# CATS-GS-Overview.net
KiCad netlist of a schematic drawn in Altium Designer
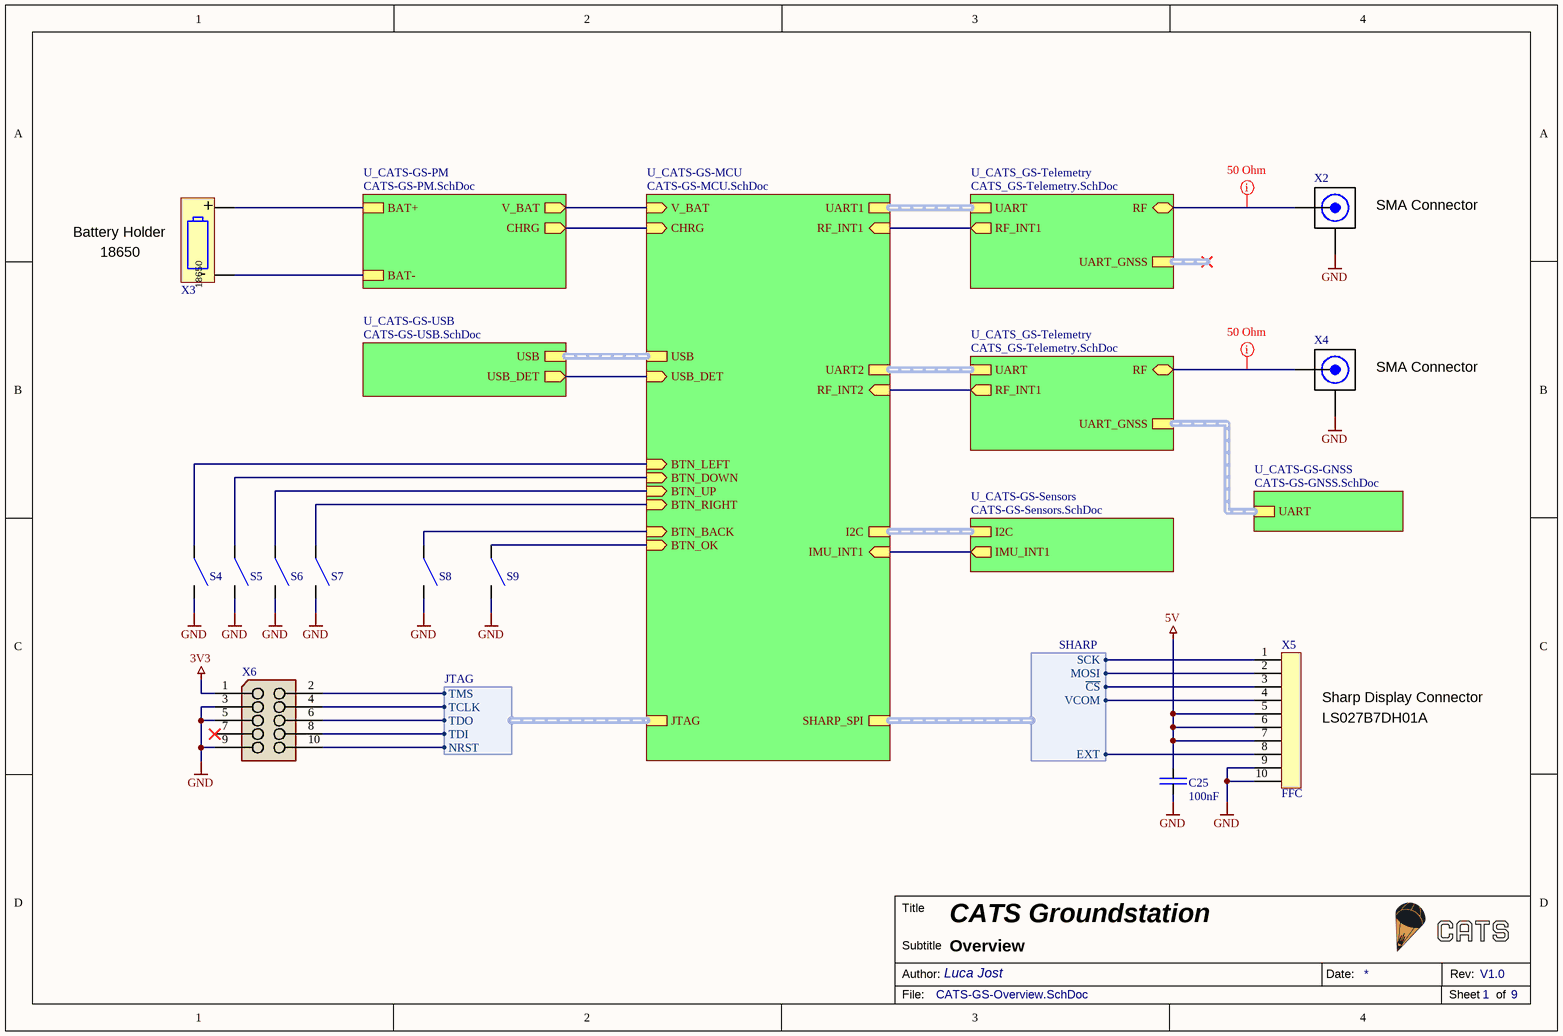
[diagram p0: CATS-GS-Overview.SchDoc]

(export (version "E")
  (design (tool "Eeschema 10.0.6"))
  (components
    (comp (ref "C25")
      (value "100nF")
      (footprint "SMD Keramikkondensator 0402")
      (description "SMD Ceramic Capacitor E6")
      (libsource (lib "CATS-EUROC") (part "E6 - 100nF"))
    )
    (comp (ref "S4")
      (value "SMD-Button")
      (footprint "SMD Button 4.2x3.2")
      (description "Button SPST")
      (libsource (lib "Switches") (part "Button 4.2mmx3.2mm"))
    )
    (comp (ref "S5")
      (value "SMD-Button")
      (footprint "SMD Button 4.2x3.2")
      (description "Button SPST")
      (libsource (lib "Switches") (part "Button 4.2mmx3.2mm"))
    )
    (comp (ref "S6")
      (value "SMD-Button")
      (footprint "SMD Button 4.2x3.2")
      (description "Button SPST")
      (libsource (lib "Switches") (part "Button 4.2mmx3.2mm"))
    )
    (comp (ref "S7")
      (value "SMD-Button")
      (footprint "SMD Button 4.2x3.2")
      (description "Button SPST")
      (libsource (lib "Switches") (part "Button 4.2mmx3.2mm"))
    )
    (comp (ref "S8")
      (value "SMD-Button")
      (footprint "SMD Button 4.2x3.2")
      (description "Button SPST")
      (libsource (lib "Switches") (part "Button 4.2mmx3.2mm"))
    )
    (comp (ref "S9")
      (value "SMD-Button")
      (footprint "SMD Button 4.2x3.2")
      (description "Button SPST")
      (libsource (lib "Switches") (part "Button 4.2mmx3.2mm"))
    )
    (comp (ref "X2")
      (value "SMA Connector")
      (footprint "SMD Connector SMA")
      (description "Female SMA Connector THT")
      (libsource (lib "Connectors") (part "SMA Connector"))
    )
    (comp (ref "X3")
      (value "18650")
      (footprint "SMD 18650 Batttery Holder")
      (description "Single 18650 Battery Holder")
      (libsource (lib "Connectors") (part "18650 Battery Holder"))
    )
    (comp (ref "X4")
      (value "SMA Connector")
      (footprint "SMD Connector SMA")
      (description "Female SMA Connector THT")
      (libsource (lib "Connectors") (part "SMA Connector"))
    )
    (comp (ref "X5")
      (value "FFC")
      (footprint "SMD Connector FFC/FPC 10Pin / 0.5mm Pitch")
      (description "10 Pin FPC/FFC Connector 0.5mm Pitch, Bottom Contact")
      (libsource (lib "Connectors") (part "FPC/FFC 10 Pin / P 0.5"))
    )
    (comp (ref "X6")
      (value "JTAG-Header (ARM-Cortex)")
      (footprint "SMD Connector 1.27mm (2x5)")
      (libsource (lib "Custom ST-Link Old") (part "X-JTAG-Header (ARM-Cortex)"))
    )
  )
  (nets
    (net (code "3") (name "/BAT+") (class "Default")
      (node (ref "X3") (pin "1") (pinfunction "+_1") (pintype "passive"))
    )
    (net (code "4") (name "/BAT-") (class "Default")
      (node (ref "X3") (pin "2") (pinfunction "-_2") (pintype "passive"))
    )
    (net (code "5") (name "/BTN_BACK") (class "Default")
      (node (ref "S8") (pin "1") (pinfunction "1_1") (pintype "passive"))
    )
    (net (code "6") (name "/BTN_DOWN") (class "Default")
      (node (ref "S5") (pin "1") (pinfunction "1_1") (pintype "passive"))
    )
    (net (code "7") (name "/BTN_LEFT") (class "Default")
      (node (ref "S4") (pin "1") (pinfunction "1_1") (pintype "passive"))
    )
    (net (code "8") (name "/BTN_OK") (class "Default")
      (node (ref "S9") (pin "1") (pinfunction "1_1") (pintype "passive"))
    )
    (net (code "9") (name "/BTN_RIGHT") (class "Default")
      (node (ref "S7") (pin "1") (pinfunction "1_1") (pintype "passive"))
    )
    (net (code "10") (name "/BTN_UP") (class "Default")
      (node (ref "S6") (pin "1") (pinfunction "1_1") (pintype "passive"))
    )
    (net (code "12") (name "/EXT") (class "Default") (node (ref "X5") (pin "8") (pintype "passive")))
    (net (code "15") (name "/MOSI") (class "Default") (node (ref "X5") (pin "2") (pintype "passive")))
    (net (code "16") (name "/NRST") (class "Default")
      (node (ref "X6") (pin "10") (pinfunction "10_10") (pintype "passive"))
    )
    (net (code "17") (name "/RF") (class "Default")
      (node (ref "X4") (pin "1") (pinfunction "RF_1") (pintype "passive"))
    )
    (net (code "18") (name "/RF_1") (class "Default")
      (node (ref "X2") (pin "1") (pinfunction "RF_1") (pintype "passive"))
    )
    (net (code "21") (name "/SCK") (class "Default") (node (ref "X5") (pin "1") (pintype "passive")))
    (net (code "22") (name "/TCLK") (class "Default")
      (node (ref "X6") (pin "4") (pinfunction "4_4") (pintype "passive"))
    )
    (net (code "23") (name "/TDI") (class "Default")
      (node (ref "X6") (pin "8") (pinfunction "8_8") (pintype "passive"))
    )
    (net (code "24") (name "/TDO") (class "Default")
      (node (ref "X6") (pin "6") (pinfunction "6_6") (pintype "passive"))
    )
    (net (code "25") (name "/TMS") (class "Default")
      (node (ref "X6") (pin "2") (pinfunction "2_2") (pintype "passive"))
    )
    (net (code "32") (name "/VCOM") (class "Default") (node (ref "X5") (pin "4") (pintype "passive")))
    (net (code "36") (name "/~{CS}") (class "Default") (node (ref "X5") (pin "3") (pintype "passive")))
    (net (code "37") (name "3V3") (class "Default")
      (node (ref "X6") (pin "1") (pinfunction "1_1") (pintype "passive"))
    )
    (net (code "38") (name "5V") (class "Default")
      (node (ref "C25") (pin "2") (pinfunction "2_2") (pintype "passive"))
      (node (ref "X5") (pin "5") (pintype "passive"))
      (node (ref "X5") (pin "6") (pintype "passive"))
      (node (ref "X5") (pin "7") (pintype "passive"))
    )
    (net (code "39") (name "GND") (class "Default")
      (node (ref "C25") (pin "1") (pinfunction "1_1") (pintype "passive"))
      (node (ref "S4") (pin "2") (pinfunction "2_2") (pintype "passive"))
      (node (ref "S5") (pin "2") (pinfunction "2_2") (pintype "passive"))
      (node (ref "S6") (pin "2") (pinfunction "2_2") (pintype "passive"))
      (node (ref "S7") (pin "2") (pinfunction "2_2") (pintype "passive"))
      (node (ref "S8") (pin "2") (pinfunction "2_2") (pintype "passive"))
      (node (ref "S9") (pin "2") (pinfunction "2_2") (pintype "passive"))
      (node (ref "X2") (pin "2") (pinfunction "RF_2") (pintype "passive"))
      (node (ref "X4") (pin "2") (pinfunction "RF_2") (pintype "passive"))
      (node (ref "X5") (pin "10") (pintype "passive"))
      (node (ref "X5") (pin "9") (pintype "passive"))
      (node (ref "X6") (pin "3") (pinfunction "3_3") (pintype "passive"))
      (node (ref "X6") (pin "5") (pinfunction "5_5") (pintype "passive"))
      (node (ref "X6") (pin "9") (pinfunction "9_9") (pintype "passive"))
    )
    (net (code "40") (name "unconnected-(X6-Pad7)") (class "Default")
      (node (ref "X6") (pin "7") (pinfunction "7_7") (pintype "passive+no_connect"))
    )
  )
)
